# trackuino_micro_sensor_chip_bat_mk2.net
KiCad netlist of a schematic drawn in EAGLE
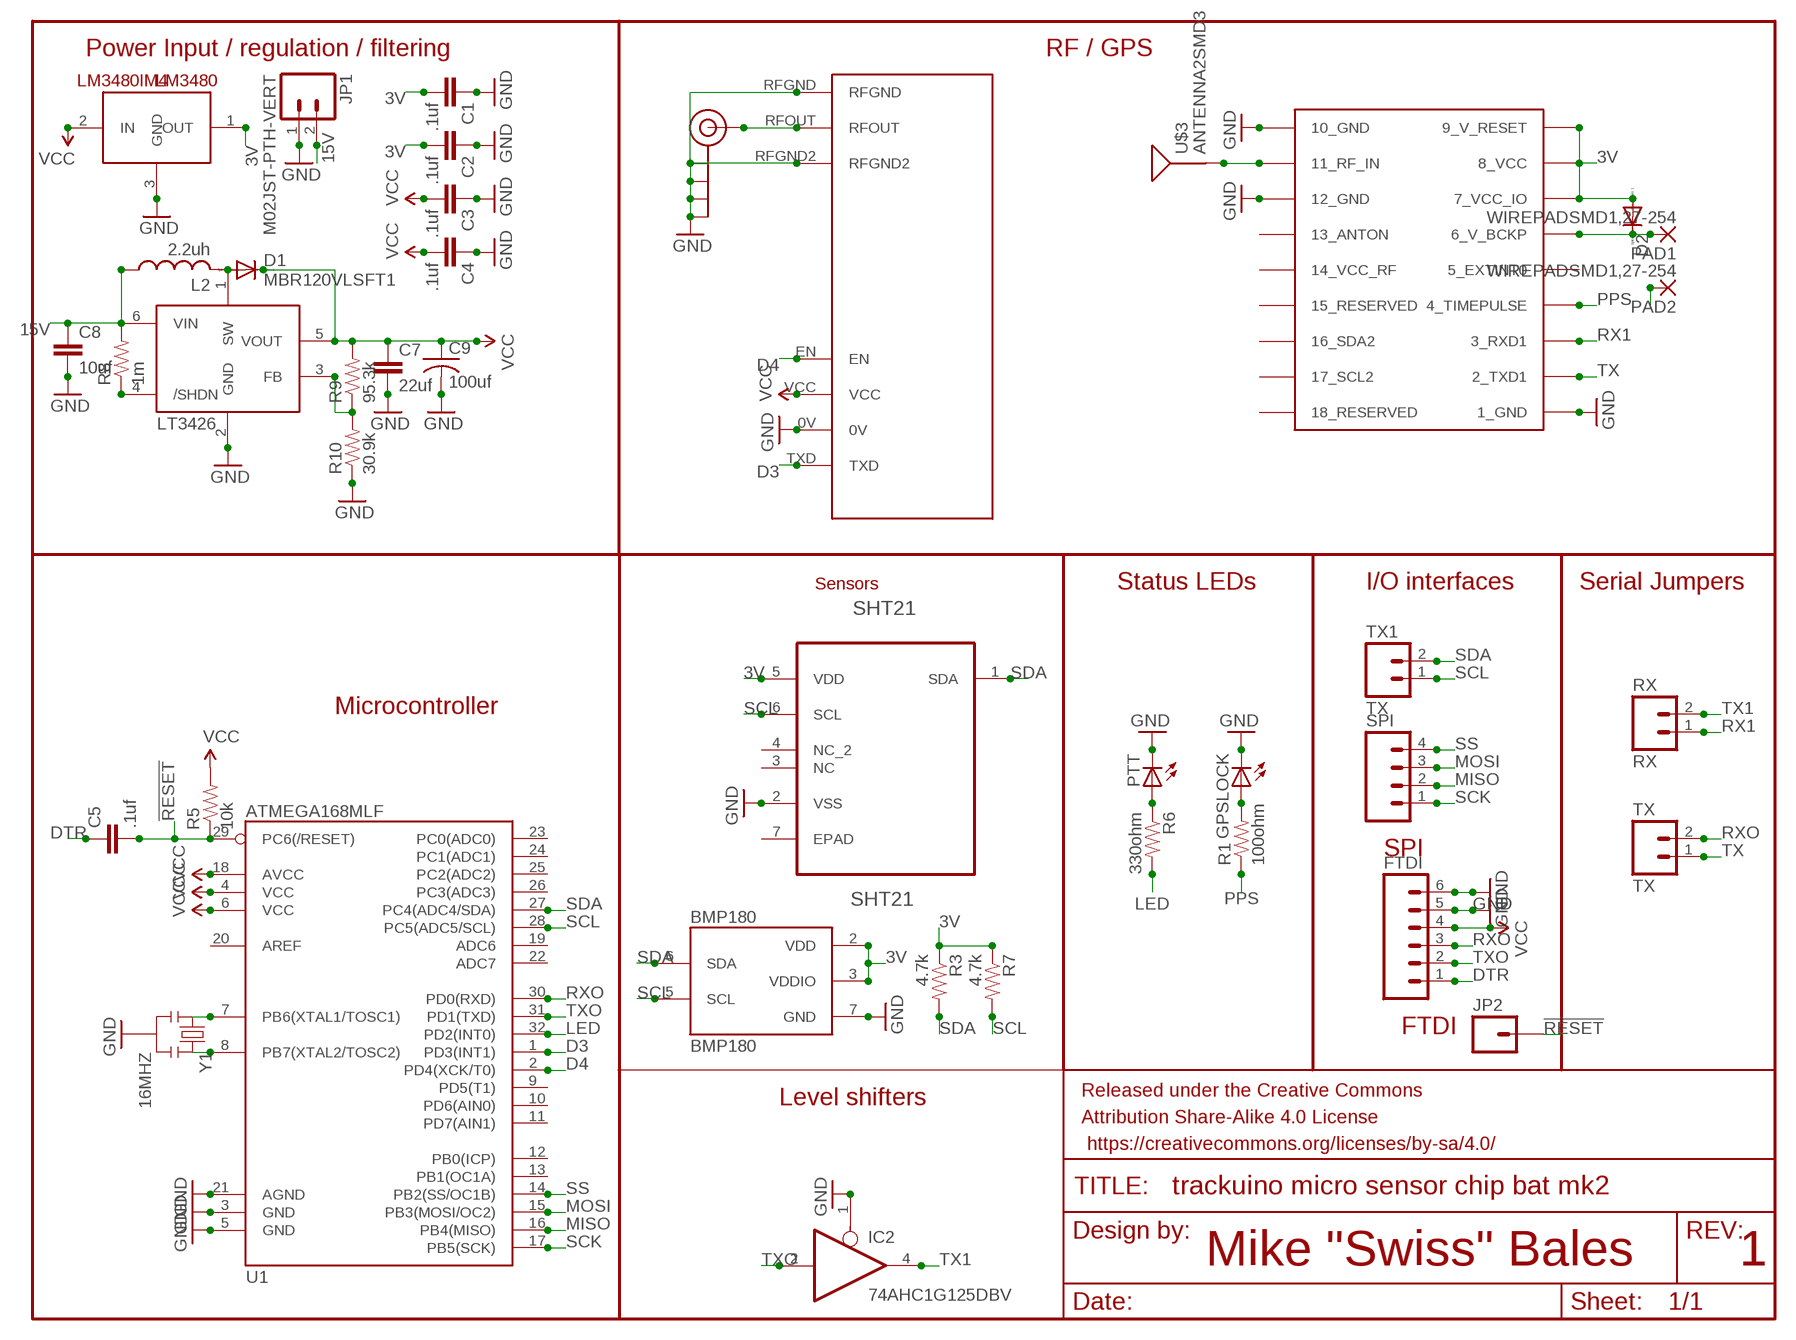
[diagram p0: schematic, sheet 1]

(export (version "E")
  (design (tool "Eeschema 10.0.6"))
  (components
    (comp (ref "BMP180")
      (value "BMP180")
      (footprint "eagle-import:BMP180")
      (libsource (lib "eagle-import") (part "BMP180"))
    )
    (comp (ref "C1")
      (value ".1uf")
      (footprint "eagle-import:0805")
      (libsource (lib "eagle-import") (part "CAP0805"))
    )
    (comp (ref "C2")
      (value ".1uf")
      (footprint "eagle-import:0805")
      (libsource (lib "eagle-import") (part "CAP0805"))
    )
    (comp (ref "C3")
      (value ".1uf")
      (footprint "eagle-import:0805")
      (libsource (lib "eagle-import") (part "CAP0805"))
    )
    (comp (ref "C4")
      (value ".1uf")
      (footprint "eagle-import:0805")
      (libsource (lib "eagle-import") (part "CAP0805"))
    )
    (comp (ref "C5")
      (value ".1uf")
      (footprint "eagle-import:0805")
      (libsource (lib "eagle-import") (part "CAP0805"))
    )
    (comp (ref "C7")
      (value "22uf")
      (footprint "eagle-import:0805")
      (libsource (lib "eagle-import") (part "CAP0805"))
    )
    (comp (ref "C8")
      (value "10uf")
      (footprint "eagle-import:0805")
      (libsource (lib "eagle-import") (part "CAP0805"))
    )
    (comp (ref "C9")
      (value "100uf")
      (footprint "eagle-import:C1206")
      (libsource (lib "eagle-import") (part "C-USC1206"))
    )
    (comp (ref "D1")
      (value "MBR120VLSFT1")
      (footprint "eagle-import:SOD123")
      (libsource (lib "eagle-import") (part "DIODE-SOD123"))
    )
    (comp (ref "D2")
      (value "DIODE-MICROMELF-R")
      (footprint "eagle-import:MICROMELF-R")
      (libsource (lib "eagle-import") (part "DIODE-MICROMELF-R"))
    )
    (comp (ref "FRAME1")
      (value "FRAME-LETTER")
      (footprint "eagle-import:CREATIVE_COMMONS")
      (libsource (lib "eagle-import") (part "FRAME-LETTER"))
    )
    (comp (ref "FTDI")
      (value "M06NO_SILK_FEMALE_PTH")
      (footprint "eagle-import:1X06_NO_SILK")
      (libsource (lib "eagle-import") (part "M06NO_SILK_FEMALE_PTH"))
    )
    (comp (ref "GPSLOCK")
      (value "LEDCHIP-LED0805")
      (footprint "eagle-import:CHIP-LED0805")
      (libsource (lib "eagle-import") (part "LEDCHIP-LED0805"))
    )
    (comp (ref "IC2")
      (value "74AHC1G125DBV")
      (footprint "eagle-import:SOT23-5")
      (libsource (lib "eagle-import") (part "741G125DBVAHC"))
    )
    (comp (ref "J$1")
      (value "SMA_EDGE")
      (footprint "eagle-import:SMA-EDGE")
      (libsource (lib "eagle-import") (part "SMA_EDGE"))
    )
    (comp (ref "JP1")
      (value "M02JST-PTH-VERT")
      (footprint "eagle-import:JST-2-PTH-VERT")
      (libsource (lib "eagle-import") (part "M02JST-PTH-VERT"))
    )
    (comp (ref "JP2")
      (value "M01PTH")
      (footprint "eagle-import:1X01")
      (libsource (lib "eagle-import") (part "M01PTH"))
    )
    (comp (ref "L2")
      (value "2.2uh")
      (footprint "eagle-import:L1812")
      (libsource (lib "eagle-import") (part "L-USL1812"))
    )
    (comp (ref "LM3480")
      (value "LM3480IM4")
      (footprint "eagle-import:SOT23-3")
      (libsource (lib "eagle-import") (part "LM3480IM4"))
    )
    (comp (ref "LT3426")
      (value "LT3426")
      (footprint "eagle-import:SOT23-6")
      (libsource (lib "eagle-import") (part "LT3426"))
    )
    (comp (ref "PAD1")
      (value "WIREPADSMD1,27-254")
      (footprint "eagle-import:SMD1,27-2,54")
      (libsource (lib "eagle-import") (part "WIREPADSMD1,27-254"))
    )
    (comp (ref "PAD2")
      (value "WIREPADSMD1,27-254")
      (footprint "eagle-import:SMD1,27-2,54")
      (libsource (lib "eagle-import") (part "WIREPADSMD1,27-254"))
    )
    (comp (ref "PTT")
      (value "LEDCHIP-LED0805")
      (footprint "eagle-import:CHIP-LED0805")
      (libsource (lib "eagle-import") (part "LEDCHIP-LED0805"))
    )
    (comp (ref "R1")
      (value "100ohm")
      (footprint "eagle-import:0805")
      (libsource (lib "eagle-import") (part "RESISTOR0805-RES"))
    )
    (comp (ref "R3")
      (value "4.7k")
      (footprint "eagle-import:0805")
      (libsource (lib "eagle-import") (part "RESISTOR0805-RES"))
    )
    (comp (ref "R5")
      (value "10k")
      (footprint "eagle-import:0805")
      (libsource (lib "eagle-import") (part "RESISTOR0805-RES"))
    )
    (comp (ref "R6")
      (value "330ohm")
      (footprint "eagle-import:0805")
      (libsource (lib "eagle-import") (part "RESISTOR0805-RES"))
    )
    (comp (ref "R7")
      (value "4.7k")
      (footprint "eagle-import:0805")
      (libsource (lib "eagle-import") (part "RESISTOR0805-RES"))
    )
    (comp (ref "R8")
      (value "1m")
      (footprint "eagle-import:0805")
      (libsource (lib "eagle-import") (part "RESISTOR0805-RES"))
    )
    (comp (ref "R9")
      (value "95.3k")
      (footprint "eagle-import:0805")
      (libsource (lib "eagle-import") (part "RESISTOR0805-RES"))
    )
    (comp (ref "R10")
      (value "30.9k")
      (footprint "eagle-import:0805")
      (libsource (lib "eagle-import") (part "RESISTOR0805-RES"))
    )
    (comp (ref "RX")
      (value "RX")
      (footprint "eagle-import:JST-2-PTH-VERT")
      (libsource (lib "eagle-import") (part "M02JST-PTH-VERT"))
    )
    (comp (ref "SHT21")
      (value "SHT21")
      (footprint "eagle-import:DFN300X300X110-7N")
      (libsource (lib "eagle-import") (part "SHT21"))
    )
    (comp (ref "SPI")
      (value "M04JST-PTH-VERT")
      (footprint "eagle-import:JST-4-PTH-VERT")
      (libsource (lib "eagle-import") (part "M04JST-PTH-VERT"))
    )
    (comp (ref "TX")
      (value "TX")
      (footprint "eagle-import:JST-2-PTH-VERT")
      (libsource (lib "eagle-import") (part "M02JST-PTH-VERT"))
    )
    (comp (ref "TX1")
      (value "TX")
      (footprint "eagle-import:JST-2-PTH-VERT")
      (libsource (lib "eagle-import") (part "M02JST-PTH-VERT"))
    )
    (comp (ref "U$1")
      (value "UBLOX_MAX")
      (footprint "eagle-import:UBLOX_MAX")
      (libsource (lib "eagle-import") (part "UBLOX_MAX"))
    )
    (comp (ref "U$2")
      (value "RADIOMETRIX-HX1")
      (footprint "eagle-import:RADIOMETRIX-HX1")
      (libsource (lib "eagle-import") (part "RADIOMETRIX-HX1"))
    )
    (comp (ref "U$3")
      (value "ANTENNA2SMD3")
      (footprint "eagle-import:ANTENNA-CHIP4")
      (libsource (lib "eagle-import") (part "ANTENNA2SMD3"))
    )
    (comp (ref "U1")
      (value "ATMEGA168MLF")
      (footprint "eagle-import:MLF32")
      (libsource (lib "eagle-import") (part "ATMEGA168MLF"))
    )
    (comp (ref "Y1")
      (value "16MHZ")
      (footprint "eagle-import:RESONATOR-SMD")
      (libsource (lib "eagle-import") (part "RESONATOR16MHZ"))
    )
  )
  (nets
    (net (code "1") (name "/3V") (class "Default")
      (node (ref "BMP180") (pin "2") (pinfunction "VDD_2") (pintype "power_in"))
      (node (ref "BMP180") (pin "3") (pinfunction "VDDIO_3") (pintype "power_in"))
      (node (ref "C1") (pin "2") (pinfunction "2_2") (pintype "passive"))
      (node (ref "C2") (pin "2") (pinfunction "2_2") (pintype "passive"))
      (node (ref "D2") (pin "A") (pinfunction "A_A") (pintype "passive"))
      (node (ref "LM3480") (pin "1") (pinfunction "OUT_1") (pintype "bidirectional"))
      (node (ref "R3") (pin "1") (pinfunction "1_1") (pintype "passive"))
      (node (ref "R7") (pin "1") (pinfunction "1_1") (pintype "passive"))
      (node (ref "SHT21") (pin "5") (pinfunction "VDD_5") (pintype "power_in"))
      (node (ref "U$1") (pin "7_VCC_IO") (pinfunction "7_VCC_IO_7_VCC_IO") (pintype "power_in"))
      (node (ref "U$1") (pin "8_VCC") (pinfunction "8_VCC_8_VCC") (pintype "power_in"))
      (node (ref "U$1") (pin "9_V_RESET") (pinfunction "9_V_RESET_9_V_RESET") (pintype "power_in"))
    )
    (net (code "2") (name "/15V") (class "Default")
      (node (ref "C8") (pin "1") (pinfunction "1_1") (pintype "passive"))
      (node (ref "JP1") (pin "2") (pinfunction "2_2") (pintype "passive"))
      (node (ref "L2") (pin "1") (pinfunction "1_1") (pintype "passive"))
      (node (ref "LT3426") (pin "6") (pinfunction "VIN_6") (pintype "input"))
      (node (ref "R8") (pin "2") (pinfunction "2_2") (pintype "passive"))
    )
    (net (code "3") (name "/D3") (class "Default")
      (node (ref "U$2") (pin "TXD") (pinfunction "TXD_TXD") (pintype "bidirectional"))
      (node (ref "U1") (pin "1") (pinfunction "PD3(INT1)_1") (pintype "bidirectional"))
    )
    (net (code "4") (name "/D4") (class "Default")
      (node (ref "U$2") (pin "EN") (pinfunction "EN_EN") (pintype "bidirectional"))
      (node (ref "U1") (pin "2") (pinfunction "PD4(XCK/T0)_2") (pintype "bidirectional"))
    )
    (net (code "5") (name "/DTR") (class "Default")
      (node (ref "C5") (pin "1") (pinfunction "1_1") (pintype "passive"))
      (node (ref "FTDI") (pin "1") (pinfunction "1_1") (pintype "passive"))
    )
    (net (code "6") (name "/LED") (class "Default")
      (node (ref "R6") (pin "2") (pinfunction "2_2") (pintype "passive"))
      (node (ref "U1") (pin "32") (pinfunction "PD2(INT0)_32") (pintype "bidirectional"))
    )
    (net (code "7") (name "/MISO") (class "Default")
      (node (ref "SPI") (pin "2") (pinfunction "2_2") (pintype "passive"))
      (node (ref "U1") (pin "16") (pinfunction "PB4(MISO)_16") (pintype "bidirectional"))
    )
    (net (code "8") (name "/MOSI") (class "Default")
      (node (ref "SPI") (pin "3") (pinfunction "3_3") (pintype "passive"))
      (node (ref "U1") (pin "15") (pinfunction "PB3(MOSI/OC2)_15") (pintype "bidirectional"))
    )
    (net (code "9") (name "/PPS") (class "Default")
      (node (ref "R1") (pin "1") (pinfunction "1_1") (pintype "passive"))
      (node (ref "U$1") (pin "4_TIMEPULSE") (pinfunction "4_TIMEPULSE_4_TIMEPULSE") (pintype "bidirectional"))
    )
    (net (code "10") (name "/RX1") (class "Default")
      (node (ref "RX") (pin "1") (pinfunction "1_1") (pintype "passive"))
      (node (ref "U$1") (pin "3_RXD1") (pinfunction "3_RXD1_3_RXD1") (pintype "bidirectional"))
    )
    (net (code "11") (name "/RXO") (class "Default")
      (node (ref "FTDI") (pin "3") (pinfunction "3_3") (pintype "passive"))
      (node (ref "TX") (pin "2") (pinfunction "2_2") (pintype "passive"))
      (node (ref "U1") (pin "30") (pinfunction "PD0(RXD)_30") (pintype "bidirectional"))
    )
    (net (code "12") (name "/SCK") (class "Default")
      (node (ref "SPI") (pin "1") (pinfunction "1_1") (pintype "passive"))
      (node (ref "U1") (pin "17") (pinfunction "PB5(SCK)_17") (pintype "bidirectional"))
    )
    (net (code "13") (name "/SCL") (class "Default")
      (node (ref "BMP180") (pin "5") (pinfunction "SCL_5") (pintype "input"))
      (node (ref "R7") (pin "2") (pinfunction "2_2") (pintype "passive"))
      (node (ref "SHT21") (pin "6") (pinfunction "SCL_6") (pintype "input"))
      (node (ref "TX1") (pin "1") (pinfunction "1_1") (pintype "passive"))
      (node (ref "U1") (pin "28") (pinfunction "PC5(ADC5/SCL)_28") (pintype "bidirectional"))
    )
    (net (code "14") (name "/SDA") (class "Default")
      (node (ref "BMP180") (pin "6") (pinfunction "SDA_6") (pintype "bidirectional"))
      (node (ref "R3") (pin "2") (pinfunction "2_2") (pintype "passive"))
      (node (ref "SHT21") (pin "1") (pinfunction "SDA_1") (pintype "bidirectional"))
      (node (ref "TX1") (pin "2") (pinfunction "2_2") (pintype "passive"))
      (node (ref "U1") (pin "27") (pinfunction "PC4(ADC4/SDA)_27") (pintype "bidirectional"))
    )
    (net (code "15") (name "/SS") (class "Default")
      (node (ref "SPI") (pin "4") (pinfunction "4_4") (pintype "passive"))
      (node (ref "U1") (pin "14") (pinfunction "PB2(SS/OC1B)_14") (pintype "bidirectional"))
    )
    (net (code "16") (name "/TX") (class "Default")
      (node (ref "TX") (pin "1") (pinfunction "1_1") (pintype "passive"))
      (node (ref "U$1") (pin "2_TXD1") (pinfunction "2_TXD1_2_TXD1") (pintype "bidirectional"))
    )
    (net (code "17") (name "/TX1") (class "Default")
      (node (ref "IC2") (pin "4") (pinfunction "O_4") (pintype "tri_state"))
      (node (ref "RX") (pin "2") (pinfunction "2_2") (pintype "passive"))
    )
    (net (code "18") (name "/TXO") (class "Default")
      (node (ref "FTDI") (pin "2") (pinfunction "2_2") (pintype "passive"))
      (node (ref "IC2") (pin "2") (pinfunction "I_2") (pintype "input"))
      (node (ref "U1") (pin "31") (pinfunction "PD1(TXD)_31") (pintype "bidirectional"))
    )
    (net (code "19") (name "/~{RESET}") (class "Default")
      (node (ref "C5") (pin "2") (pinfunction "2_2") (pintype "passive"))
      (node (ref "JP2") (pin "1") (pinfunction "1_1") (pintype "passive"))
      (node (ref "R5") (pin "1") (pinfunction "1_1") (pintype "passive"))
      (node (ref "U1") (pin "29") (pinfunction "PC6(/RESET)_29") (pintype "bidirectional"))
    )
    (net (code "20") (name "GND") (class "Default")
      (node (ref "BMP180") (pin "7") (pinfunction "GND_7") (pintype "power_in"))
      (node (ref "C1") (pin "1") (pinfunction "1_1") (pintype "passive"))
      (node (ref "C2") (pin "1") (pinfunction "1_1") (pintype "passive"))
      (node (ref "C3") (pin "1") (pinfunction "1_1") (pintype "passive"))
      (node (ref "C4") (pin "1") (pinfunction "1_1") (pintype "passive"))
      (node (ref "C7") (pin "2") (pinfunction "2_2") (pintype "passive"))
      (node (ref "C8") (pin "2") (pinfunction "2_2") (pintype "passive"))
      (node (ref "C9") (pin "2") (pinfunction "2_2") (pintype "passive"))
      (node (ref "FTDI") (pin "5") (pinfunction "5_5") (pintype "passive"))
      (node (ref "FTDI") (pin "6") (pinfunction "6_6") (pintype "passive"))
      (node (ref "GPSLOCK") (pin "C") (pinfunction "C_C") (pintype "passive"))
      (node (ref "IC2") (pin "1") (pinfunction "OE_1") (pintype "input"))
      (node (ref "J$1") (pin "GND@0") (pinfunction "GND_GND@0") (pintype "bidirectional"))
      (node (ref "J$1") (pin "GND@1") (pinfunction "GND_GND@1") (pintype "bidirectional"))
      (node (ref "J$1") (pin "GND@2") (pinfunction "GND_GND@2") (pintype "bidirectional"))
      (node (ref "J$1") (pin "GND@3") (pinfunction "GND_GND@3") (pintype "bidirectional"))
      (node (ref "JP1") (pin "1") (pinfunction "1_1") (pintype "passive"))
      (node (ref "LM3480") (pin "3") (pinfunction "GND_3") (pintype "bidirectional"))
      (node (ref "LT3426") (pin "2") (pinfunction "GND_2") (pintype "power_in"))
      (node (ref "PAD2") (pin "1") (pinfunction "P_1") (pintype "passive"))
      (node (ref "PTT") (pin "C") (pinfunction "C_C") (pintype "passive"))
      (node (ref "R10") (pin "1") (pinfunction "1_1") (pintype "passive"))
      (node (ref "SHT21") (pin "2") (pinfunction "VSS_2") (pintype "power_in"))
      (node (ref "U$1") (pin "10_GND") (pinfunction "10_GND_10_GND") (pintype "power_in"))
      (node (ref "U$1") (pin "12_GND") (pinfunction "12_GND_12_GND") (pintype "power_in"))
      (node (ref "U$1") (pin "1_GND") (pinfunction "1_GND_1_GND") (pintype "power_in"))
      (node (ref "U$2") (pin "0V") (pinfunction "0V_0V") (pintype "bidirectional"))
      (node (ref "U$2") (pin "RFGND") (pinfunction "RFGND_RFGND") (pintype "bidirectional"))
      (node (ref "U$2") (pin "RFGND2") (pinfunction "RFGND2_RFGND2") (pintype "bidirectional"))
      (node (ref "U1") (pin "21") (pinfunction "AGND_21") (pintype "bidirectional"))
      (node (ref "U1") (pin "3") (pinfunction "GND_3") (pintype "bidirectional"))
      (node (ref "U1") (pin "5") (pinfunction "GND_5") (pintype "bidirectional"))
      (node (ref "Y1") (pin "2") (pinfunction "2_2") (pintype "passive"))
    )
    (net (code "21") (name "Net-(GPSLOCK-PadA)") (class "Default")
      (node (ref "GPSLOCK") (pin "A") (pinfunction "A_A") (pintype "passive"))
      (node (ref "R1") (pin "2") (pinfunction "2_2") (pintype "passive"))
    )
    (net (code "22") (name "Net-(J$1-SIGNAL)") (class "Default")
      (node (ref "J$1") (pin "SIG") (pinfunction "SIGNAL_SIG") (pintype "bidirectional"))
      (node (ref "U$2") (pin "RFOUT") (pinfunction "RFOUT_RFOUT") (pintype "bidirectional"))
    )
    (net (code "23") (name "Net-(LT3426-FB)") (class "Default")
      (node (ref "LT3426") (pin "3") (pinfunction "FB_3") (pintype "input"))
      (node (ref "R10") (pin "2") (pinfunction "2_2") (pintype "passive"))
      (node (ref "R9") (pin "1") (pinfunction "1_1") (pintype "passive"))
    )
    (net (code "24") (name "Net-(LT3426-SW)") (class "Default")
      (node (ref "D1") (pin "A") (pinfunction "A_A") (pintype "passive"))
      (node (ref "L2") (pin "2") (pinfunction "2_2") (pintype "passive"))
      (node (ref "LT3426") (pin "1") (pinfunction "SW_1") (pintype "output"))
    )
    (net (code "25") (name "Net-(LT3426-{slash}SHDN)") (class "Default")
      (node (ref "LT3426") (pin "4") (pinfunction "/SHDN_4") (pintype "input"))
      (node (ref "R8") (pin "1") (pinfunction "1_1") (pintype "passive"))
    )
    (net (code "26") (name "Net-(PAD1-P)") (class "Default")
      (node (ref "D2") (pin "C") (pinfunction "C_C") (pintype "passive"))
      (node (ref "PAD1") (pin "1") (pinfunction "P_1") (pintype "passive"))
      (node (ref "U$1") (pin "6_V_BCKP") (pinfunction "6_V_BCKP_6_V_BCKP") (pintype "bidirectional"))
    )
    (net (code "27") (name "Net-(PTT-PadA)") (class "Default")
      (node (ref "PTT") (pin "A") (pinfunction "A_A") (pintype "passive"))
      (node (ref "R6") (pin "1") (pinfunction "1_1") (pintype "passive"))
    )
    (net (code "28") (name "Net-(U$3-SIGNAL)") (class "Default")
      (node (ref "U$1") (pin "11_RF_IN") (pinfunction "11_RF_IN_11_RF_IN") (pintype "bidirectional"))
      (node (ref "U$3") (pin "SIG") (pinfunction "SIGNAL_SIG") (pintype "bidirectional"))
    )
    (net (code "29") (name "Net-(U1-PB6(XTAL1{slash}TOSC1))") (class "Default")
      (node (ref "U1") (pin "7") (pinfunction "PB6(XTAL1/TOSC1)_7") (pintype "bidirectional"))
      (node (ref "Y1") (pin "1") (pinfunction "1_1") (pintype "passive"))
    )
    (net (code "30") (name "Net-(U1-PB7(XTAL2{slash}TOSC2))") (class "Default")
      (node (ref "U1") (pin "8") (pinfunction "PB7(XTAL2/TOSC2)_8") (pintype "bidirectional"))
      (node (ref "Y1") (pin "3") (pinfunction "3_3") (pintype "passive"))
    )
    (net (code "31") (name "VCC") (class "Default")
      (node (ref "C3") (pin "2") (pinfunction "2_2") (pintype "passive"))
      (node (ref "C4") (pin "2") (pinfunction "2_2") (pintype "passive"))
      (node (ref "C7") (pin "1") (pinfunction "1_1") (pintype "passive"))
      (node (ref "C9") (pin "1") (pinfunction "1_1") (pintype "passive"))
      (node (ref "D1") (pin "C") (pinfunction "C_C") (pintype "passive"))
      (node (ref "FTDI") (pin "4") (pinfunction "4_4") (pintype "passive"))
      (node (ref "LM3480") (pin "2") (pinfunction "IN_2") (pintype "bidirectional"))
      (node (ref "LT3426") (pin "5") (pinfunction "VOUT_5") (pintype "output"))
      (node (ref "R5") (pin "2") (pinfunction "2_2") (pintype "passive"))
      (node (ref "R9") (pin "2") (pinfunction "2_2") (pintype "passive"))
      (node (ref "U$2") (pin "VCC") (pinfunction "VCC_VCC") (pintype "bidirectional"))
      (node (ref "U1") (pin "18") (pinfunction "AVCC_18") (pintype "bidirectional"))
      (node (ref "U1") (pin "4") (pinfunction "VCC_4") (pintype "bidirectional"))
      (node (ref "U1") (pin "6") (pinfunction "VCC_6") (pintype "bidirectional"))
    )
    (net (code "32") (name "unconnected-(SHT21-EPAD-Pad7)") (class "Default")
      (node (ref "SHT21") (pin "7") (pinfunction "EPAD_7") (pintype "passive"))
    )
    (net (code "33") (name "unconnected-(SHT21-NC-Pad3)") (class "Default")
      (node (ref "SHT21") (pin "3") (pinfunction "NC_3") (pintype "no_connect"))
    )
    (net (code "34") (name "unconnected-(SHT21-NC_2-Pad4)") (class "Default")
      (node (ref "SHT21") (pin "4") (pinfunction "NC_2_4") (pintype "no_connect"))
    )
    (net (code "35") (name "unconnected-(U$1-Pad5_EXTINT0)") (class "Default")
      (node (ref "U$1") (pin "5_EXTINT0") (pinfunction "5_EXTINT0_5_EXTINT0") (pintype "bidirectional"))
    )
    (net (code "36") (name "unconnected-(U$1-Pad13_ANTON)") (class "Default")
      (node (ref "U$1") (pin "13_ANTON") (pinfunction "13_ANTON_13_ANTON") (pintype "bidirectional"))
    )
    (net (code "37") (name "unconnected-(U$1-Pad14_VCC_RF)") (class "Default")
      (node (ref "U$1") (pin "14_VCC_RF") (pinfunction "14_VCC_RF_14_VCC_RF") (pintype "bidirectional"))
    )
    (net (code "38") (name "unconnected-(U$1-Pad15_RESERVED)") (class "Default")
      (node (ref "U$1") (pin "15_RESERVED") (pinfunction "15_RESERVED_15_RESERVED") (pintype "bidirectional"))
    )
    (net (code "39") (name "unconnected-(U$1-Pad16_SDA2)") (class "Default")
      (node (ref "U$1") (pin "16_SDA2") (pinfunction "16_SDA2_16_SDA2") (pintype "bidirectional"))
    )
    (net (code "40") (name "unconnected-(U$1-Pad17_SCL2)") (class "Default")
      (node (ref "U$1") (pin "17_SCL2") (pinfunction "17_SCL2_17_SCL2") (pintype "bidirectional"))
    )
    (net (code "41") (name "unconnected-(U$1-Pad18_RESERVED)") (class "Default")
      (node (ref "U$1") (pin "18_RESERVED") (pinfunction "18_RESERVED_18_RESERVED") (pintype "bidirectional"))
    )
    (net (code "42") (name "unconnected-(U1-ADC6-Pad19)") (class "Default")
      (node (ref "U1") (pin "19") (pinfunction "ADC6_19") (pintype "bidirectional"))
    )
    (net (code "43") (name "unconnected-(U1-ADC7-Pad22)") (class "Default")
      (node (ref "U1") (pin "22") (pinfunction "ADC7_22") (pintype "bidirectional"))
    )
    (net (code "44") (name "unconnected-(U1-AREF-Pad20)") (class "Default")
      (node (ref "U1") (pin "20") (pinfunction "AREF_20") (pintype "bidirectional"))
    )
    (net (code "45") (name "unconnected-(U1-PB0(ICP)-Pad12)") (class "Default")
      (node (ref "U1") (pin "12") (pinfunction "PB0(ICP)_12") (pintype "bidirectional"))
    )
    (net (code "46") (name "unconnected-(U1-PB1(OC1A)-Pad13)") (class "Default")
      (node (ref "U1") (pin "13") (pinfunction "PB1(OC1A)_13") (pintype "bidirectional"))
    )
    (net (code "47") (name "unconnected-(U1-PC0(ADC0)-Pad23)") (class "Default")
      (node (ref "U1") (pin "23") (pinfunction "PC0(ADC0)_23") (pintype "bidirectional"))
    )
    (net (code "48") (name "unconnected-(U1-PC1(ADC1)-Pad24)") (class "Default")
      (node (ref "U1") (pin "24") (pinfunction "PC1(ADC1)_24") (pintype "bidirectional"))
    )
    (net (code "49") (name "unconnected-(U1-PC2(ADC2)-Pad25)") (class "Default")
      (node (ref "U1") (pin "25") (pinfunction "PC2(ADC2)_25") (pintype "bidirectional"))
    )
    (net (code "50") (name "unconnected-(U1-PC3(ADC3)-Pad26)") (class "Default")
      (node (ref "U1") (pin "26") (pinfunction "PC3(ADC3)_26") (pintype "bidirectional"))
    )
    (net (code "51") (name "unconnected-(U1-PD5(T1)-Pad9)") (class "Default")
      (node (ref "U1") (pin "9") (pinfunction "PD5(T1)_9") (pintype "bidirectional"))
    )
    (net (code "52") (name "unconnected-(U1-PD6(AIN0)-Pad10)") (class "Default")
      (node (ref "U1") (pin "10") (pinfunction "PD6(AIN0)_10") (pintype "bidirectional"))
    )
    (net (code "53") (name "unconnected-(U1-PD7(AIN1)-Pad11)") (class "Default")
      (node (ref "U1") (pin "11") (pinfunction "PD7(AIN1)_11") (pintype "bidirectional"))
    )
  )
)
